# PeripheralCircuit.net
KiCad netlist of a schematic drawn in Altium Designer
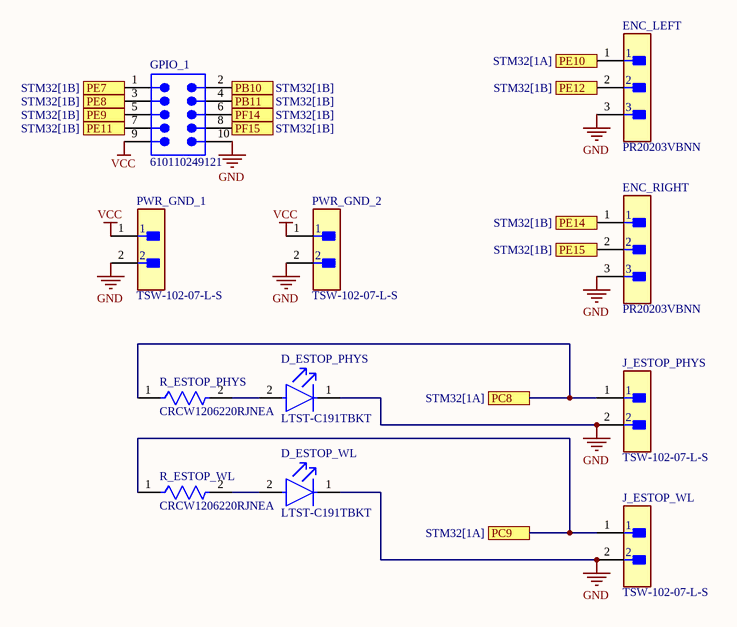
[diagram p0: PeripheralCircuit.SchDoc]

(export (version "E")
  (design (tool "Eeschema 10.0.6"))
  (components
    (comp (ref "D_ESTOP_PHYS")
      (value "LTST-C191TBKT")
      (footprint "FP-LTST-C191TBKT-MFG")
      (description "LED BLUE CLEAR CHIP SMD")
      (libsource (lib "Altium Content Vault") (part "8706943c75ba83719d021d2fdc84c58"))
    )
    (comp (ref "D_ESTOP_WL")
      (value "LTST-C191TBKT")
      (footprint "FP-LTST-C191TBKT-MFG")
      (description "LED BLUE CLEAR CHIP SMD")
      (libsource (lib "Altium Content Vault") (part "8706943c75ba83719d021d2fdc84c58"))
    )
    (comp (ref "ENC_LEFT")
      (value "PR20203VBNN")
      (footprint "FP-PR20203VBNN-MFG")
      (description "CONN HEADER VERT 3POS 2.54MM")
      (fields
        (field (name "OCTOPART") "https://octopart.com/pr20203vbnn-metz+connect-87667116")
        (field (name "MANUFACTURER") "Metz Connect")
      )
      (libsource (lib "Altium Content Vault") (part "0d3f023dd272f625e17a2be33dea85f"))
    )
    (comp (ref "ENC_RIGHT")
      (value "PR20203VBNN")
      (footprint "FP-PR20203VBNN-MFG")
      (description "CONN HEADER VERT 3POS 2.54MM")
      (fields
        (field (name "OCTOPART") "https://octopart.com/pr20203vbnn-metz+connect-87667116")
        (field (name "MANUFACTURER") "Metz Connect")
      )
      (libsource (lib "Altium Content Vault") (part "0d3f023dd272f625e17a2be33dea85f"))
    )
    (comp (ref "GPIO_1")
      (value "610110249121")
      (footprint "610110249121")
      (libsource (lib "Altium Content Vault") (part "Header_Male_2R_10P"))
    )
    (comp (ref "J_ESTOP_PHYS")
      (value "TSW-102-07-L-S")
      (footprint "FP-TSW-102-07-L-S-MFG")
      (description "CONN HEADER VERT 2POS 2.54MM")
      (libsource (lib "Altium Content Vault") (part "3bc925449376181038e59eaffc5286c"))
    )
    (comp (ref "J_ESTOP_WL")
      (value "TSW-102-07-L-S")
      (footprint "FP-TSW-102-07-L-S-MFG")
      (description "CONN HEADER VERT 2POS 2.54MM")
      (libsource (lib "Altium Content Vault") (part "3bc925449376181038e59eaffc5286c"))
    )
    (comp (ref "PWR_GND_1")
      (value "TSW-102-07-L-S")
      (footprint "FP-TSW-102-07-L-S-MFG")
      (description "CONN HEADER VERT 2POS 2.54MM")
      (libsource (lib "Altium Content Vault") (part "3bc925449376181038e59eaffc5286c"))
    )
    (comp (ref "PWR_GND_2")
      (value "TSW-102-07-L-S")
      (footprint "FP-TSW-102-07-L-S-MFG")
      (description "CONN HEADER VERT 2POS 2.54MM")
      (libsource (lib "Altium Content Vault") (part "3bc925449376181038e59eaffc5286c"))
    )
    (comp (ref "R_ESTOP_PHYS")
      (value "CRCW1206220RJNEA")
      (footprint "FP-CRCW1206-e3-IPC_C")
      (description "RES Thick Film, 220Ω, 5%, 0.25W, 200ppm/°C, 1206")
      (fields (field (name "TOLERANCE") "5%"))
      (libsource (lib "Altium Content Vault") (part "1029c3af85768c4190bb7ad29bc67b5"))
    )
    (comp (ref "R_ESTOP_WL")
      (value "CRCW1206220RJNEA")
      (footprint "FP-CRCW1206-e3-IPC_C")
      (description "RES Thick Film, 220Ω, 5%, 0.25W, 200ppm/°C, 1206")
      (fields (field (name "TOLERANCE") "5%"))
      (libsource (lib "Altium Content Vault") (part "1029c3af85768c4190bb7ad29bc67b5"))
    )
  )
  (nets
    (net (code "1") (name "/PB10") (class "Default")
      (node (ref "GPIO_1") (pin "2") (pinfunction "2_2") (pintype "passive"))
    )
    (net (code "2") (name "/PB11") (class "Default")
      (node (ref "GPIO_1") (pin "4") (pinfunction "4_4") (pintype "passive"))
    )
    (net (code "3") (name "/PC8") (class "Default")
      (node (ref "J_ESTOP_PHYS") (pin "1") (pinfunction "1_1") (pintype "passive"))
      (node (ref "R_ESTOP_PHYS") (pin "1") (pinfunction "1_1") (pintype "passive"))
    )
    (net (code "4") (name "/PC9") (class "Default")
      (node (ref "J_ESTOP_WL") (pin "1") (pinfunction "1_1") (pintype "passive"))
      (node (ref "R_ESTOP_WL") (pin "1") (pinfunction "1_1") (pintype "passive"))
    )
    (net (code "5") (name "/PE7") (class "Default")
      (node (ref "GPIO_1") (pin "1") (pinfunction "1_1") (pintype "passive"))
    )
    (net (code "6") (name "/PE8") (class "Default")
      (node (ref "GPIO_1") (pin "3") (pinfunction "3_3") (pintype "passive"))
    )
    (net (code "7") (name "/PE9") (class "Default")
      (node (ref "GPIO_1") (pin "5") (pinfunction "5_5") (pintype "passive"))
    )
    (net (code "8") (name "/PE10") (class "Default")
      (node (ref "ENC_LEFT") (pin "1") (pinfunction "1_1") (pintype "passive"))
    )
    (net (code "9") (name "/PE11") (class "Default")
      (node (ref "GPIO_1") (pin "7") (pinfunction "7_7") (pintype "passive"))
    )
    (net (code "10") (name "/PE12") (class "Default")
      (node (ref "ENC_LEFT") (pin "2") (pinfunction "2_2") (pintype "passive"))
    )
    (net (code "11") (name "/PE14") (class "Default")
      (node (ref "ENC_RIGHT") (pin "1") (pinfunction "1_1") (pintype "passive"))
    )
    (net (code "12") (name "/PE15") (class "Default")
      (node (ref "ENC_RIGHT") (pin "2") (pinfunction "2_2") (pintype "passive"))
    )
    (net (code "13") (name "/PF14") (class "Default")
      (node (ref "GPIO_1") (pin "6") (pinfunction "6_6") (pintype "passive"))
    )
    (net (code "14") (name "/PF15") (class "Default")
      (node (ref "GPIO_1") (pin "8") (pinfunction "8_8") (pintype "passive"))
    )
    (net (code "15") (name "GND") (class "Default")
      (node (ref "D_ESTOP_PHYS") (pin "1") (pinfunction "C_1") (pintype "passive"))
      (node (ref "D_ESTOP_WL") (pin "1") (pinfunction "C_1") (pintype "passive"))
      (node (ref "ENC_LEFT") (pin "3") (pinfunction "3_3") (pintype "passive"))
      (node (ref "ENC_RIGHT") (pin "3") (pinfunction "3_3") (pintype "passive"))
      (node (ref "GPIO_1") (pin "10") (pinfunction "10_10") (pintype "passive"))
      (node (ref "J_ESTOP_PHYS") (pin "2") (pinfunction "2_2") (pintype "passive"))
      (node (ref "J_ESTOP_WL") (pin "2") (pinfunction "2_2") (pintype "passive"))
      (node (ref "PWR_GND_1") (pin "2") (pinfunction "2_2") (pintype "passive"))
      (node (ref "PWR_GND_2") (pin "2") (pinfunction "2_2") (pintype "passive"))
    )
    (net (code "16") (name "Net-(D_ESTOP_PHYS-A)") (class "Default")
      (node (ref "D_ESTOP_PHYS") (pin "2") (pinfunction "A_2") (pintype "passive"))
      (node (ref "R_ESTOP_PHYS") (pin "2") (pinfunction "2_2") (pintype "passive"))
    )
    (net (code "17") (name "Net-(D_ESTOP_WL-A)") (class "Default")
      (node (ref "D_ESTOP_WL") (pin "2") (pinfunction "A_2") (pintype "passive"))
      (node (ref "R_ESTOP_WL") (pin "2") (pinfunction "2_2") (pintype "passive"))
    )
    (net (code "18") (name "VCC") (class "Default")
      (node (ref "GPIO_1") (pin "9") (pinfunction "9_9") (pintype "passive"))
      (node (ref "PWR_GND_1") (pin "1") (pinfunction "1_1") (pintype "passive"))
      (node (ref "PWR_GND_2") (pin "1") (pinfunction "1_1") (pintype "passive"))
    )
  )
)
